# Adafruit_MPU6050.net
KiCad netlist of a schematic drawn in EAGLE
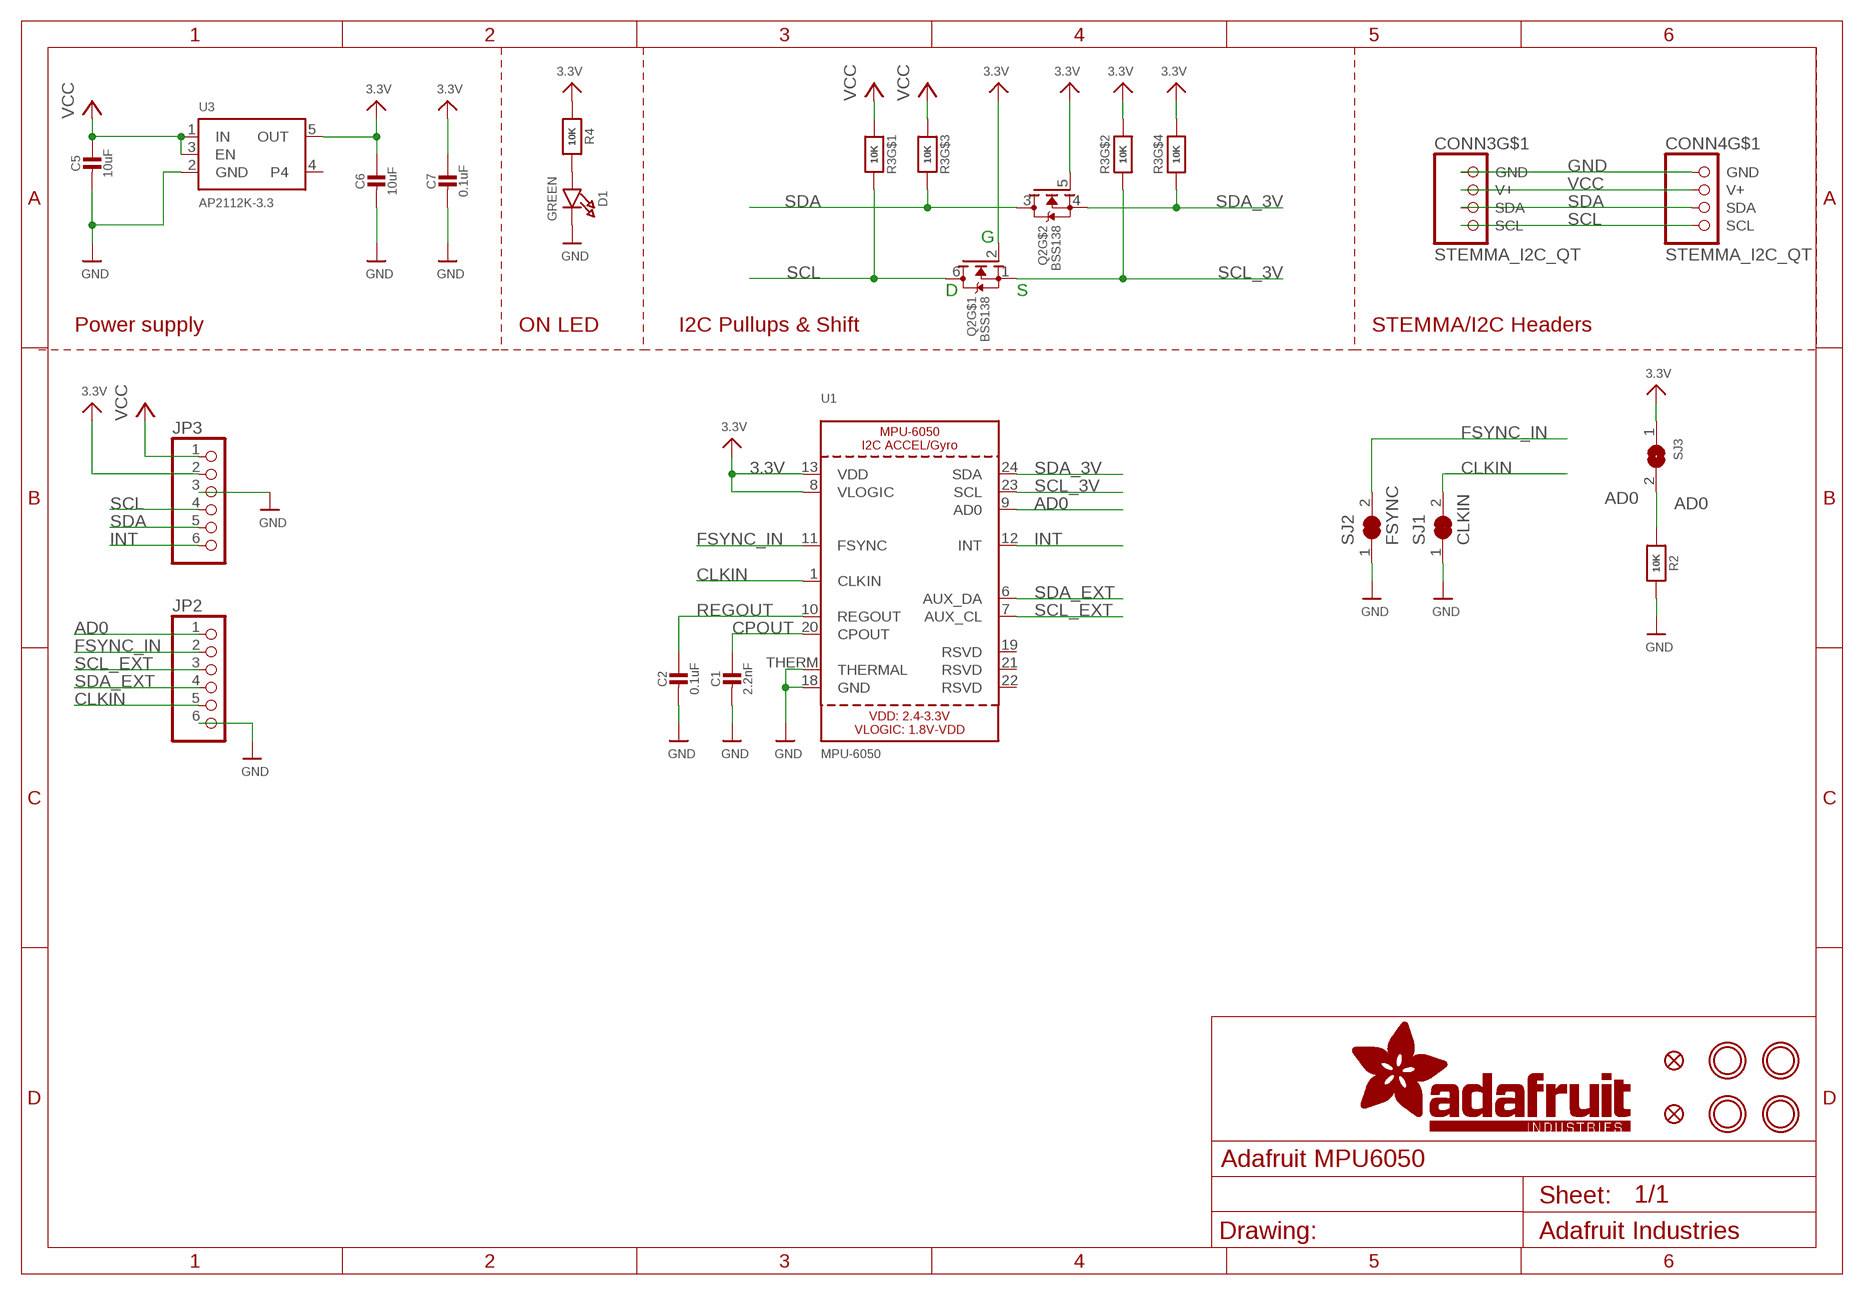
[diagram p0: schematic, sheet 1]

(export (version "E")
  (design (tool "Eeschema 10.0.6"))
  (components
    (comp (ref "C1")
      (value "2.2nF")
      (footprint "eagle-import:0603-NO")
      (libsource (lib "eagle-import") (part "CAP_CERAMIC0603_NO"))
    )
    (comp (ref "C2")
      (value "0.1uF")
      (footprint "eagle-import:0603-NO")
      (libsource (lib "eagle-import") (part "CAP_CERAMIC0603_NO"))
    )
    (comp (ref "C5")
      (value "10uF")
      (footprint "eagle-import:0805-NO")
      (libsource (lib "eagle-import") (part "CAP_CERAMIC0805-NOOUTLINE"))
    )
    (comp (ref "C6")
      (value "10uF")
      (footprint "eagle-import:0805-NO")
      (libsource (lib "eagle-import") (part "CAP_CERAMIC0805-NOOUTLINE"))
    )
    (comp (ref "C7")
      (value "0.1uF")
      (footprint "eagle-import:0603-NO")
      (libsource (lib "eagle-import") (part "CAP_CERAMIC0603_NO"))
    )
    (comp (ref "CONN3")
      (value "STEMMA_I2C_QT")
      (footprint "eagle-import:JST_SH4")
      (libsource (lib "eagle-import") (part "STEMMA_I2C_QT"))
    )
    (comp (ref "CONN4")
      (value "STEMMA_I2C_QT")
      (footprint "eagle-import:JST_SH4")
      (libsource (lib "eagle-import") (part "STEMMA_I2C_QT"))
    )
    (comp (ref "D1")
      (value "GREEN")
      (footprint "eagle-import:CHIPLED_0603_NOOUTLINE")
      (libsource (lib "eagle-import") (part "LED0603_NOOUTLINE"))
    )
    (comp (ref "FID3")
      (value "FIDUCIAL_1MM")
      (footprint "eagle-import:FIDUCIAL_1MM")
      (libsource (lib "eagle-import") (part "FIDUCIAL_1MM"))
    )
    (comp (ref "FID4")
      (value "FIDUCIAL_1MM")
      (footprint "eagle-import:FIDUCIAL_1MM")
      (libsource (lib "eagle-import") (part "FIDUCIAL_1MM"))
    )
    (comp (ref "JP2")
      (value "HEADER-1X6ROUND")
      (footprint "eagle-import:1X06_ROUND")
      (libsource (lib "eagle-import") (part "HEADER-1X6ROUND"))
    )
    (comp (ref "JP3")
      (value "HEADER-1X670MIL")
      (footprint "eagle-import:1X06_ROUND_70")
      (libsource (lib "eagle-import") (part "HEADER-1X670MIL"))
    )
    (comp (ref "Q2")
      (value "BSS138")
      (footprint "eagle-import:SOT363")
      (libsource (lib "eagle-import") (part "MOSFET-N_DUAL"))
    )
    (comp (ref "R2")
      (value "10K")
      (footprint "eagle-import:0603-NO")
      (libsource (lib "eagle-import") (part "RESISTOR_0603_NOOUT"))
    )
    (comp (ref "R3")
      (value "10K")
      (footprint "eagle-import:RESPACK_4X0603")
      (libsource (lib "eagle-import") (part "RESISTOR_4PACK"))
    )
    (comp (ref "R4")
      (value "10K")
      (footprint "eagle-import:0603-NO")
      (libsource (lib "eagle-import") (part "RESISTOR_0603_NOOUT"))
    )
    (comp (ref "SJ1")
      (value "CLKIN")
      (footprint "eagle-import:SOLDERJUMPER_CLOSEDWIRE")
      (libsource (lib "eagle-import") (part "SOLDERJUMPER_CLOSED"))
    )
    (comp (ref "SJ2")
      (value "FSYNC")
      (footprint "eagle-import:SOLDERJUMPER_CLOSEDWIRE")
      (libsource (lib "eagle-import") (part "SOLDERJUMPER_CLOSED"))
    )
    (comp (ref "SJ3")
      (value "SOLDERJUMPER")
      (footprint "eagle-import:SOLDERJUMPER_ARROW_NOPASTE")
      (libsource (lib "eagle-import") (part "SOLDERJUMPER"))
    )
    (comp (ref "U$39")
      (value "MOUNTINGHOLE2.5")
      (footprint "eagle-import:MOUNTINGHOLE_2.5_PLATED")
      (libsource (lib "eagle-import") (part "MOUNTINGHOLE2.5"))
    )
    (comp (ref "U$40")
      (value "MOUNTINGHOLE2.5")
      (footprint "eagle-import:MOUNTINGHOLE_2.5_PLATED")
      (libsource (lib "eagle-import") (part "MOUNTINGHOLE2.5"))
    )
    (comp (ref "U$42")
      (value "MOUNTINGHOLE2.5")
      (footprint "eagle-import:MOUNTINGHOLE_2.5_PLATED")
      (libsource (lib "eagle-import") (part "MOUNTINGHOLE2.5"))
    )
    (comp (ref "U$43")
      (value "MOUNTINGHOLE2.5")
      (footprint "eagle-import:MOUNTINGHOLE_2.5_PLATED")
      (libsource (lib "eagle-import") (part "MOUNTINGHOLE2.5"))
    )
    (comp (ref "U1")
      (value "MPU-6050")
      (footprint "eagle-import:QFN24_4MM_SMSC")
      (libsource (lib "eagle-import") (part "MPU-6050"))
    )
    (comp (ref "U3")
      (value "AP2112K-3.3")
      (footprint "eagle-import:SOT23-5")
      (libsource (lib "eagle-import") (part "VREG_SOT23-5"))
    )
  )
  (nets
    (net (code "1") (name "/AD0") (class "Default")
      (node (ref "JP2") (pin "1") (pinfunction "1_1") (pintype "passive"))
      (node (ref "R2") (pin "1") (pinfunction "1_1") (pintype "passive"))
      (node (ref "SJ3") (pin "2") (pinfunction "2_2") (pintype "passive"))
      (node (ref "U1") (pin "9") (pinfunction "AD0_9") (pintype "input"))
    )
    (net (code "2") (name "/CLKIN") (class "Default")
      (node (ref "JP2") (pin "5") (pinfunction "5_5") (pintype "passive"))
      (node (ref "SJ1") (pin "2") (pinfunction "2_2") (pintype "passive"))
      (node (ref "U1") (pin "1") (pinfunction "CLKIN_1") (pintype "input"))
    )
    (net (code "3") (name "/CPOUT") (class "Default")
      (node (ref "C1") (pin "1") (pinfunction "1_1") (pintype "passive"))
      (node (ref "U1") (pin "20") (pinfunction "CPOUT_20") (pintype "passive"))
    )
    (net (code "4") (name "/FSYNC_IN") (class "Default")
      (node (ref "JP2") (pin "2") (pinfunction "2_2") (pintype "passive"))
      (node (ref "SJ2") (pin "2") (pinfunction "2_2") (pintype "passive"))
      (node (ref "U1") (pin "11") (pinfunction "FSYNC_11") (pintype "input"))
    )
    (net (code "5") (name "/INT") (class "Default")
      (node (ref "JP3") (pin "6") (pinfunction "6_6") (pintype "passive"))
      (node (ref "U1") (pin "12") (pinfunction "INT_12") (pintype "output"))
    )
    (net (code "6") (name "/REGOUT") (class "Default")
      (node (ref "C2") (pin "1") (pinfunction "1_1") (pintype "passive"))
      (node (ref "U1") (pin "10") (pinfunction "REGOUT_10") (pintype "passive"))
    )
    (net (code "7") (name "/SCL") (class "Default")
      (node (ref "CONN3") (pin "4") (pinfunction "SCL_4") (pintype "passive"))
      (node (ref "CONN4") (pin "4") (pinfunction "SCL_4") (pintype "passive"))
      (node (ref "JP3") (pin "4") (pinfunction "4_4") (pintype "passive"))
      (node (ref "Q2") (pin "6") (pinfunction "D_6") (pintype "bidirectional"))
      (node (ref "R3") (pin "8") (pinfunction "2_8") (pintype "passive"))
    )
    (net (code "8") (name "/SCL_3V") (class "Default")
      (node (ref "Q2") (pin "1") (pinfunction "S_1") (pintype "bidirectional"))
      (node (ref "R3") (pin "7") (pinfunction "2_7") (pintype "passive"))
      (node (ref "U1") (pin "23") (pinfunction "SCL_23") (pintype "bidirectional"))
    )
    (net (code "9") (name "/SCL_EXT") (class "Default")
      (node (ref "JP2") (pin "3") (pinfunction "3_3") (pintype "passive"))
      (node (ref "U1") (pin "7") (pinfunction "AUX_CL_7") (pintype "bidirectional"))
    )
    (net (code "10") (name "/SDA") (class "Default")
      (node (ref "CONN3") (pin "3") (pinfunction "SDA_3") (pintype "passive"))
      (node (ref "CONN4") (pin "3") (pinfunction "SDA_3") (pintype "passive"))
      (node (ref "JP3") (pin "5") (pinfunction "5_5") (pintype "passive"))
      (node (ref "Q2") (pin "3") (pinfunction "D_3") (pintype "bidirectional"))
      (node (ref "R3") (pin "6") (pinfunction "2_6") (pintype "passive"))
    )
    (net (code "11") (name "/SDA_3V") (class "Default")
      (node (ref "Q2") (pin "4") (pinfunction "S_4") (pintype "bidirectional"))
      (node (ref "R3") (pin "5") (pinfunction "2_5") (pintype "passive"))
      (node (ref "U1") (pin "24") (pinfunction "SDA_24") (pintype "bidirectional"))
    )
    (net (code "12") (name "/SDA_EXT") (class "Default")
      (node (ref "JP2") (pin "4") (pinfunction "4_4") (pintype "passive"))
      (node (ref "U1") (pin "6") (pinfunction "AUX_DA_6") (pintype "bidirectional"))
    )
    (net (code "13") (name "3.3V") (class "Default")
      (node (ref "C6") (pin "1") (pinfunction "1_1") (pintype "passive"))
      (node (ref "C7") (pin "1") (pinfunction "1_1") (pintype "passive"))
      (node (ref "JP3") (pin "2") (pinfunction "2_2") (pintype "passive"))
      (node (ref "Q2") (pin "2") (pinfunction "G_2") (pintype "bidirectional"))
      (node (ref "Q2") (pin "5") (pinfunction "G_5") (pintype "bidirectional"))
      (node (ref "R3") (pin "2") (pinfunction "1_2") (pintype "passive"))
      (node (ref "R3") (pin "4") (pinfunction "1_4") (pintype "passive"))
      (node (ref "R4") (pin "1") (pinfunction "1_1") (pintype "passive"))
      (node (ref "SJ3") (pin "1") (pinfunction "1_1") (pintype "passive"))
      (node (ref "U1") (pin "13") (pinfunction "VDD_13") (pintype "power_in"))
      (node (ref "U1") (pin "8") (pinfunction "VLOGIC_8") (pintype "power_in"))
      (node (ref "U3") (pin "5") (pinfunction "OUT_5") (pintype "power_in"))
    )
    (net (code "14") (name "GND") (class "Default")
      (node (ref "C1") (pin "2") (pinfunction "2_2") (pintype "passive"))
      (node (ref "C2") (pin "2") (pinfunction "2_2") (pintype "passive"))
      (node (ref "C5") (pin "2") (pinfunction "2_2") (pintype "passive"))
      (node (ref "C6") (pin "2") (pinfunction "2_2") (pintype "passive"))
      (node (ref "C7") (pin "2") (pinfunction "2_2") (pintype "passive"))
      (node (ref "CONN3") (pin "1") (pinfunction "GND_1") (pintype "passive"))
      (node (ref "CONN4") (pin "1") (pinfunction "GND_1") (pintype "passive"))
      (node (ref "D1") (pin "C") (pinfunction "C_C") (pintype "passive"))
      (node (ref "JP2") (pin "6") (pinfunction "6_6") (pintype "passive"))
      (node (ref "JP3") (pin "3") (pinfunction "3_3") (pintype "passive"))
      (node (ref "R2") (pin "2") (pinfunction "2_2") (pintype "passive"))
      (node (ref "SJ1") (pin "1") (pinfunction "1_1") (pintype "passive"))
      (node (ref "SJ2") (pin "1") (pinfunction "1_1") (pintype "passive"))
      (node (ref "U1") (pin "18") (pinfunction "GND_18") (pintype "power_in"))
      (node (ref "U1") (pin "THERM") (pinfunction "THERMAL_THERM") (pintype "power_in"))
      (node (ref "U3") (pin "2") (pinfunction "GND_2") (pintype "power_in"))
    )
    (net (code "15") (name "Net-(D1-PadA)") (class "Default")
      (node (ref "D1") (pin "A") (pinfunction "A_A") (pintype "passive"))
      (node (ref "R4") (pin "2") (pinfunction "2_2") (pintype "passive"))
    )
    (net (code "16") (name "VCC") (class "Default")
      (node (ref "C5") (pin "1") (pinfunction "1_1") (pintype "passive"))
      (node (ref "CONN3") (pin "2") (pinfunction "V+_2") (pintype "passive"))
      (node (ref "CONN4") (pin "2") (pinfunction "V+_2") (pintype "passive"))
      (node (ref "JP3") (pin "1") (pinfunction "1_1") (pintype "passive"))
      (node (ref "R3") (pin "1") (pinfunction "1_1") (pintype "passive"))
      (node (ref "R3") (pin "3") (pinfunction "1_3") (pintype "passive"))
      (node (ref "U3") (pin "1") (pinfunction "IN_1") (pintype "power_in"))
      (node (ref "U3") (pin "3") (pinfunction "EN_3") (pintype "input"))
    )
    (net (code "17") (name "unconnected-(U1-RSVD-Pad19)") (class "Default")
      (node (ref "U1") (pin "19") (pinfunction "RSVD_19") (pintype "no_connect"))
    )
    (net (code "18") (name "unconnected-(U1-RSVD-Pad21)") (class "Default")
      (node (ref "U1") (pin "21") (pinfunction "RSVD_21") (pintype "no_connect"))
    )
    (net (code "19") (name "unconnected-(U1-RSVD-Pad22)") (class "Default")
      (node (ref "U1") (pin "22") (pinfunction "RSVD_22") (pintype "no_connect"))
    )
    (net (code "20") (name "unconnected-(U3-P4-Pad4)") (class "Default")
      (node (ref "U3") (pin "4") (pinfunction "P4_4") (pintype "bidirectional"))
    )
  )
)
